# card-terminal.net
KiCad netlist of a schematic drawn in EAGLE
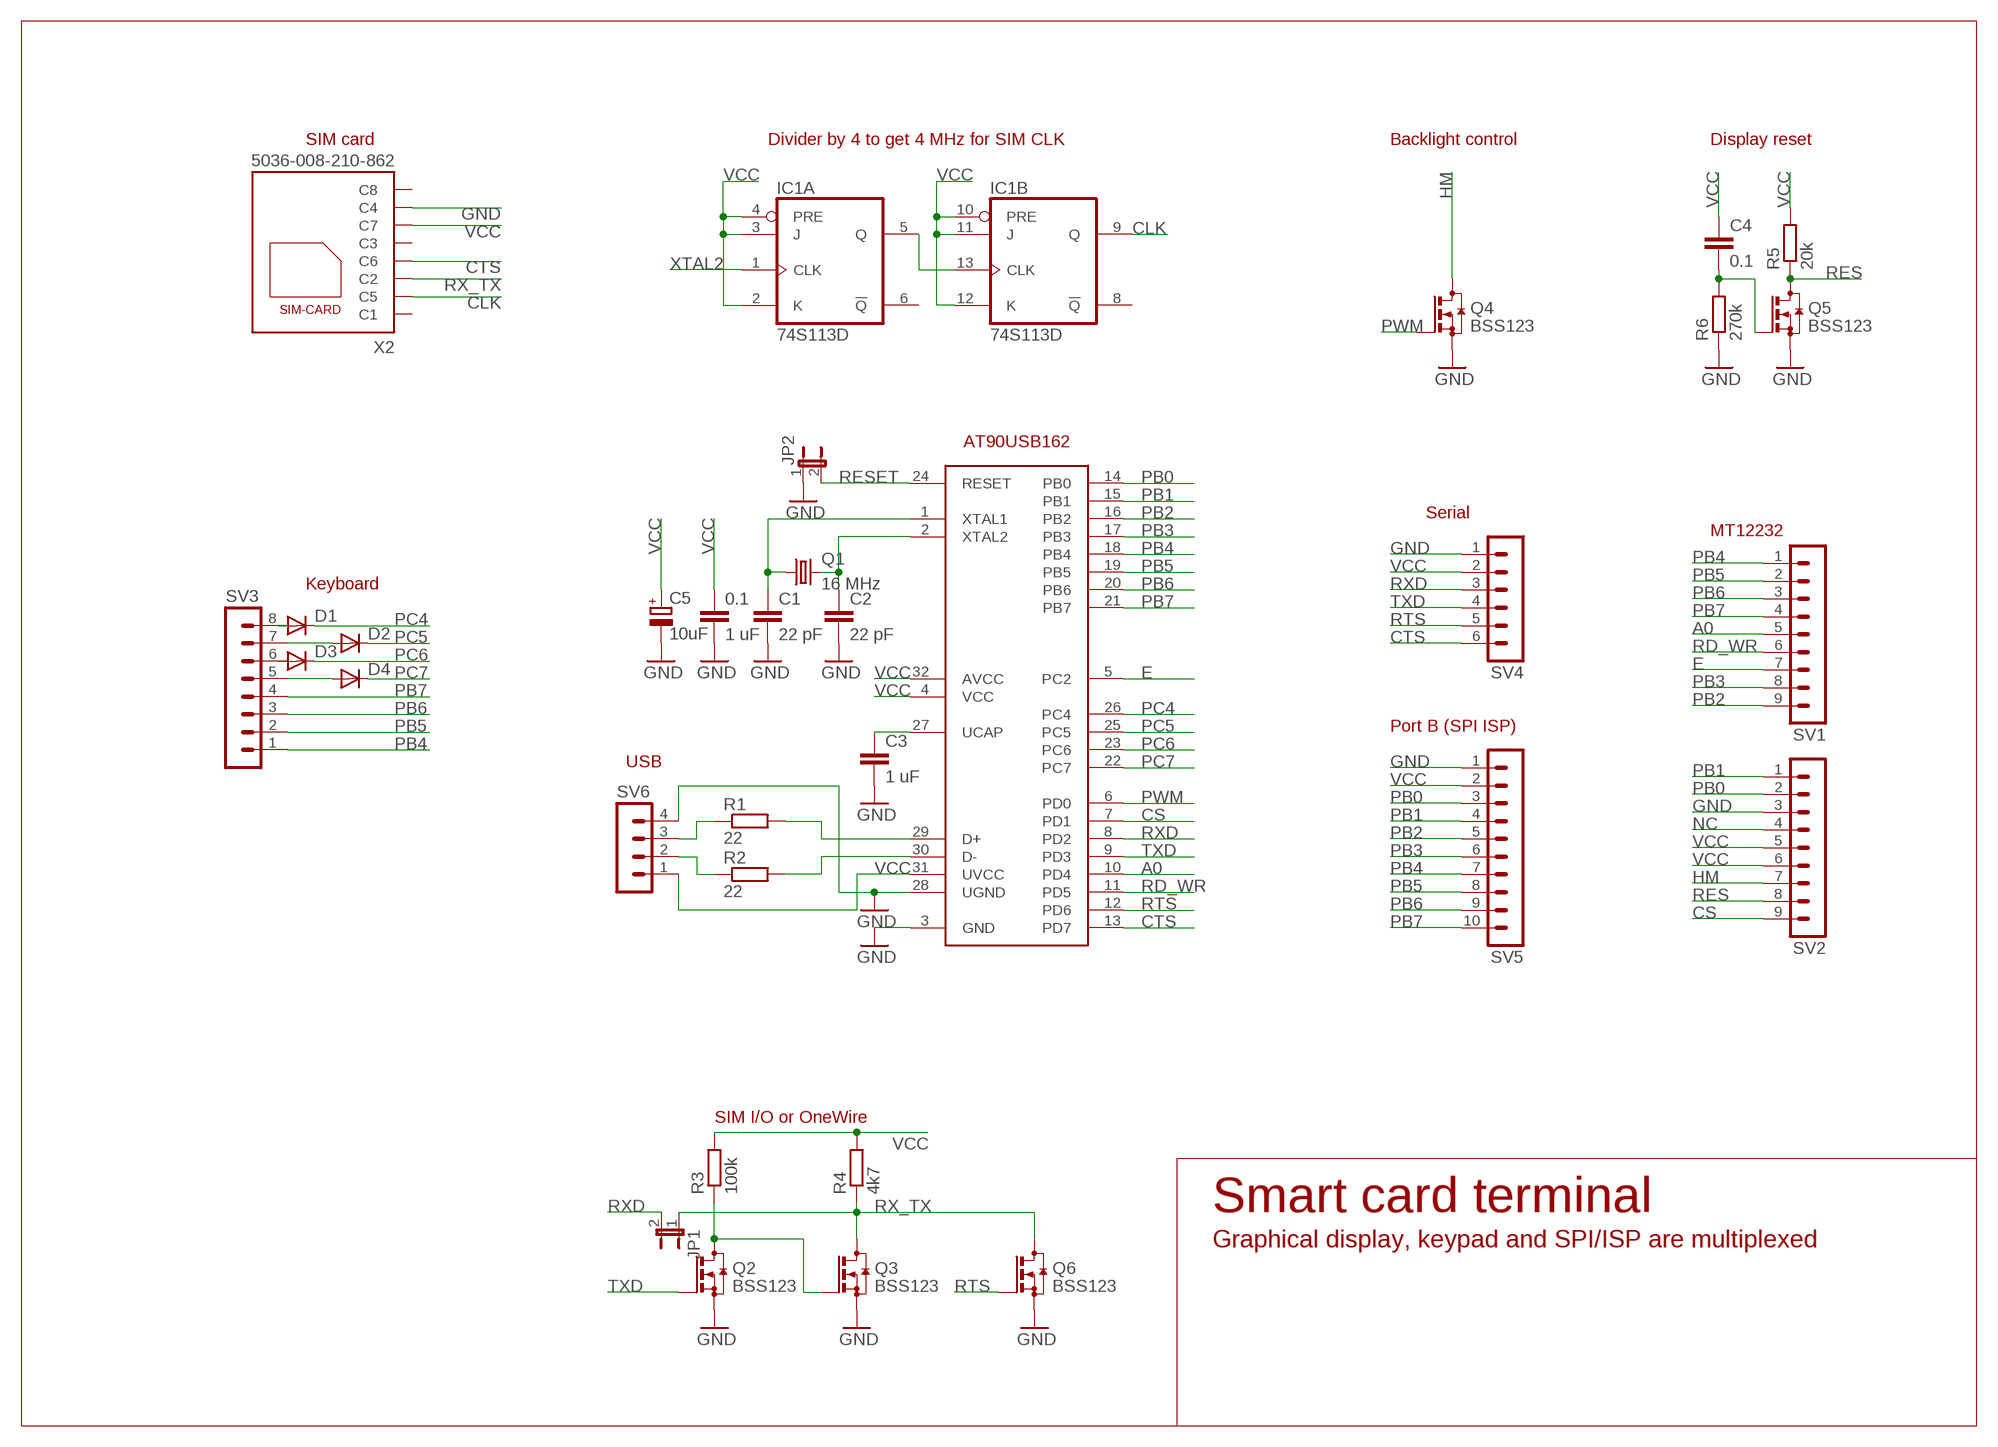
[diagram p0: schematic, sheet 1]

(export (version "E")
  (design (tool "Eeschema 10.0.6"))
  (components
    (comp (ref "0.1")
      (value "1 uF")
      (footprint "eagle-import:C0805")
      (libsource (lib "eagle-import") (part "C-EUC0805"))
    )
    (comp (ref "C1")
      (value "22 pF")
      (footprint "eagle-import:C0805")
      (libsource (lib "eagle-import") (part "C-EUC0805"))
    )
    (comp (ref "C2")
      (value "22 pF")
      (footprint "eagle-import:C0805")
      (libsource (lib "eagle-import") (part "C-EUC0805"))
    )
    (comp (ref "C3")
      (value "1 uF")
      (footprint "eagle-import:C0805")
      (libsource (lib "eagle-import") (part "C-EUC0805"))
    )
    (comp (ref "C4")
      (value "0.1")
      (footprint "eagle-import:C0805")
      (libsource (lib "eagle-import") (part "C-EUC0805"))
    )
    (comp (ref "C5")
      (value "10uF")
      (footprint "eagle-import:153CLV-0505")
      (libsource (lib "eagle-import") (part "CPOL-EU153CLV-0505"))
    )
    (comp (ref "D1")
      (value "DIODE-MINIMELF")
      (footprint "eagle-import:MINIMELF")
      (libsource (lib "eagle-import") (part "DIODE-MINIMELF"))
    )
    (comp (ref "D2")
      (value "DIODE-MINIMELF")
      (footprint "eagle-import:MINIMELF")
      (libsource (lib "eagle-import") (part "DIODE-MINIMELF"))
    )
    (comp (ref "D3")
      (value "DIODE-MINIMELF")
      (footprint "eagle-import:MINIMELF")
      (libsource (lib "eagle-import") (part "DIODE-MINIMELF"))
    )
    (comp (ref "D4")
      (value "DIODE-MINIMELF")
      (footprint "eagle-import:MINIMELF")
      (libsource (lib "eagle-import") (part "DIODE-MINIMELF"))
    )
    (comp (ref "IC1")
      (value "74S113D")
      (footprint "eagle-import:SO14")
      (libsource (lib "eagle-import") (part "74113DS"))
    )
    (comp (ref "JP1")
      (value "JP1E")
      (footprint "eagle-import:JP1")
      (libsource (lib "eagle-import") (part "JP1E"))
    )
    (comp (ref "JP2")
      (value "JP1E")
      (footprint "eagle-import:JP1")
      (libsource (lib "eagle-import") (part "JP1E"))
    )
    (comp (ref "Q1")
      (value "16 MHz")
      (footprint "eagle-import:HC49_S")
      (libsource (lib "eagle-import") (part "CRYSTALHC49S"))
    )
    (comp (ref "Q2")
      (value "BSS123")
      (footprint "eagle-import:SOT23")
      (libsource (lib "eagle-import") (part "BSS123"))
    )
    (comp (ref "Q3")
      (value "BSS123")
      (footprint "eagle-import:SOT23")
      (libsource (lib "eagle-import") (part "BSS123"))
    )
    (comp (ref "Q4")
      (value "BSS123")
      (footprint "eagle-import:SOT23")
      (libsource (lib "eagle-import") (part "BSS123"))
    )
    (comp (ref "Q5")
      (value "BSS123")
      (footprint "eagle-import:SOT23")
      (libsource (lib "eagle-import") (part "BSS123"))
    )
    (comp (ref "Q6")
      (value "BSS123")
      (footprint "eagle-import:SOT23")
      (libsource (lib "eagle-import") (part "BSS123"))
    )
    (comp (ref "R1")
      (value "22")
      (footprint "eagle-import:M0805")
      (libsource (lib "eagle-import") (part "R-EU_M0805"))
    )
    (comp (ref "R2")
      (value "22")
      (footprint "eagle-import:M0805")
      (libsource (lib "eagle-import") (part "R-EU_M0805"))
    )
    (comp (ref "R3")
      (value "100k")
      (footprint "eagle-import:M0805")
      (libsource (lib "eagle-import") (part "R-EU_M0805"))
    )
    (comp (ref "R4")
      (value "4k7")
      (footprint "eagle-import:M0805")
      (libsource (lib "eagle-import") (part "R-EU_M0805"))
    )
    (comp (ref "R5")
      (value "20k")
      (footprint "eagle-import:M0805")
      (libsource (lib "eagle-import") (part "R-EU_M0805"))
    )
    (comp (ref "R6")
      (value "270k")
      (footprint "eagle-import:M0805")
      (libsource (lib "eagle-import") (part "R-EU_M0805"))
    )
    (comp (ref "SV1")
      (value "MA09-1W")
      (footprint "eagle-import:MA09-1W")
      (libsource (lib "eagle-import") (part "MA09-1W"))
    )
    (comp (ref "SV2")
      (value "MA09-1W")
      (footprint "eagle-import:MA09-1W")
      (libsource (lib "eagle-import") (part "MA09-1W"))
    )
    (comp (ref "SV3")
      (value "MA08-1")
      (footprint "eagle-import:MA08-1")
      (libsource (lib "eagle-import") (part "MA08-1"))
    )
    (comp (ref "SV4")
      (value "MA06-1")
      (footprint "eagle-import:MA06-1")
      (libsource (lib "eagle-import") (part "MA06-1"))
    )
    (comp (ref "SV5")
      (value "MA10-1W")
      (footprint "eagle-import:MA10-1W")
      (libsource (lib "eagle-import") (part "MA10-1W"))
    )
    (comp (ref "SV6")
      (value "MA04-1")
      (footprint "eagle-import:MA04-1")
      (libsource (lib "eagle-import") (part "MA04-1"))
    )
    (comp (ref "U$1")
      (value "AT90USB162")
      (footprint "eagle-import:VQFP32")
      (libsource (lib "eagle-import") (part "AT90USB162"))
    )
    (comp (ref "X2")
      (value "5036-008-210-862")
      (footprint "eagle-import:5036_008_210_862")
      (libsource (lib "eagle-import") (part "5036-008-210-862"))
    )
  )
  (nets
    (net (code "1") (name "/A0") (class "Default")
      (node (ref "SV1") (pin "5") (pinfunction "5_5") (pintype "passive"))
      (node (ref "U$1") (pin "10") (pinfunction "PD4_10") (pintype "bidirectional"))
    )
    (net (code "2") (name "/CLK") (class "Default")
      (node (ref "IC1") (pin "9") (pinfunction "Q_9") (pintype "output"))
      (node (ref "X2") (pin "C5") (pinfunction "C5_C5") (pintype "passive"))
    )
    (net (code "3") (name "/CS") (class "Default")
      (node (ref "SV2") (pin "9") (pinfunction "9_9") (pintype "passive"))
      (node (ref "U$1") (pin "7") (pinfunction "PD1_7") (pintype "bidirectional"))
    )
    (net (code "4") (name "/CTS") (class "Default")
      (node (ref "SV4") (pin "6") (pinfunction "6_6") (pintype "passive"))
      (node (ref "U$1") (pin "13") (pinfunction "PD7_13") (pintype "bidirectional"))
      (node (ref "X2") (pin "C6") (pinfunction "C6_C6") (pintype "passive"))
    )
    (net (code "5") (name "/E") (class "Default")
      (node (ref "SV1") (pin "7") (pinfunction "7_7") (pintype "passive"))
      (node (ref "U$1") (pin "5") (pinfunction "PC2_5") (pintype "bidirectional"))
    )
    (net (code "6") (name "/HM") (class "Default")
      (node (ref "Q4") (pin "3") (pinfunction "D_3") (pintype "passive"))
      (node (ref "SV2") (pin "7") (pinfunction "7_7") (pintype "passive"))
    )
    (net (code "7") (name "/NC") (class "Default")
      (node (ref "SV2") (pin "4") (pinfunction "4_4") (pintype "passive"))
    )
    (net (code "8") (name "/PB0") (class "Default")
      (node (ref "SV2") (pin "2") (pinfunction "2_2") (pintype "passive"))
      (node (ref "SV5") (pin "3") (pinfunction "3_3") (pintype "passive"))
      (node (ref "U$1") (pin "14") (pinfunction "PB0_14") (pintype "bidirectional"))
    )
    (net (code "9") (name "/PB1") (class "Default")
      (node (ref "SV2") (pin "1") (pinfunction "1_1") (pintype "passive"))
      (node (ref "SV5") (pin "4") (pinfunction "4_4") (pintype "passive"))
      (node (ref "U$1") (pin "15") (pinfunction "PB1_15") (pintype "bidirectional"))
    )
    (net (code "10") (name "/PB2") (class "Default")
      (node (ref "SV1") (pin "9") (pinfunction "9_9") (pintype "passive"))
      (node (ref "SV5") (pin "5") (pinfunction "5_5") (pintype "passive"))
      (node (ref "U$1") (pin "16") (pinfunction "PB2_16") (pintype "bidirectional"))
    )
    (net (code "11") (name "/PB3") (class "Default")
      (node (ref "SV1") (pin "8") (pinfunction "8_8") (pintype "passive"))
      (node (ref "SV5") (pin "6") (pinfunction "6_6") (pintype "passive"))
      (node (ref "U$1") (pin "17") (pinfunction "PB3_17") (pintype "bidirectional"))
    )
    (net (code "12") (name "/PB4") (class "Default")
      (node (ref "SV1") (pin "1") (pinfunction "1_1") (pintype "passive"))
      (node (ref "SV3") (pin "1") (pinfunction "1_1") (pintype "passive"))
      (node (ref "SV5") (pin "7") (pinfunction "7_7") (pintype "passive"))
      (node (ref "U$1") (pin "18") (pinfunction "PB4_18") (pintype "bidirectional"))
    )
    (net (code "13") (name "/PB5") (class "Default")
      (node (ref "SV1") (pin "2") (pinfunction "2_2") (pintype "passive"))
      (node (ref "SV3") (pin "2") (pinfunction "2_2") (pintype "passive"))
      (node (ref "SV5") (pin "8") (pinfunction "8_8") (pintype "passive"))
      (node (ref "U$1") (pin "19") (pinfunction "PB5_19") (pintype "bidirectional"))
    )
    (net (code "14") (name "/PB6") (class "Default")
      (node (ref "SV1") (pin "3") (pinfunction "3_3") (pintype "passive"))
      (node (ref "SV3") (pin "3") (pinfunction "3_3") (pintype "passive"))
      (node (ref "SV5") (pin "9") (pinfunction "9_9") (pintype "passive"))
      (node (ref "U$1") (pin "20") (pinfunction "PB6_20") (pintype "bidirectional"))
    )
    (net (code "15") (name "/PB7") (class "Default")
      (node (ref "SV1") (pin "4") (pinfunction "4_4") (pintype "passive"))
      (node (ref "SV3") (pin "4") (pinfunction "4_4") (pintype "passive"))
      (node (ref "SV5") (pin "10") (pinfunction "10_10") (pintype "passive"))
      (node (ref "U$1") (pin "21") (pinfunction "PB7_21") (pintype "bidirectional"))
    )
    (net (code "16") (name "/PC4") (class "Default")
      (node (ref "D1") (pin "C") (pinfunction "C_C") (pintype "passive"))
      (node (ref "U$1") (pin "26") (pinfunction "PC4_26") (pintype "bidirectional"))
    )
    (net (code "17") (name "/PC5") (class "Default")
      (node (ref "D2") (pin "C") (pinfunction "C_C") (pintype "passive"))
      (node (ref "U$1") (pin "25") (pinfunction "PC5_25") (pintype "bidirectional"))
    )
    (net (code "18") (name "/PC6") (class "Default")
      (node (ref "D3") (pin "C") (pinfunction "C_C") (pintype "passive"))
      (node (ref "U$1") (pin "23") (pinfunction "PC6_23") (pintype "bidirectional"))
    )
    (net (code "19") (name "/PC7") (class "Default")
      (node (ref "D4") (pin "C") (pinfunction "C_C") (pintype "passive"))
      (node (ref "U$1") (pin "22") (pinfunction "PC7_22") (pintype "bidirectional"))
    )
    (net (code "20") (name "/PWM") (class "Default")
      (node (ref "Q4") (pin "1") (pinfunction "G_1") (pintype "passive"))
      (node (ref "U$1") (pin "6") (pinfunction "PD0_6") (pintype "bidirectional"))
    )
    (net (code "21") (name "/RD_WR") (class "Default")
      (node (ref "SV1") (pin "6") (pinfunction "6_6") (pintype "passive"))
      (node (ref "U$1") (pin "11") (pinfunction "PD5_11") (pintype "bidirectional"))
    )
    (net (code "22") (name "/RES") (class "Default")
      (node (ref "Q5") (pin "3") (pinfunction "D_3") (pintype "passive"))
      (node (ref "R5") (pin "1") (pinfunction "1_1") (pintype "passive"))
      (node (ref "SV2") (pin "8") (pinfunction "8_8") (pintype "passive"))
    )
    (net (code "23") (name "/RESET") (class "Default")
      (node (ref "JP2") (pin "2") (pinfunction "2_2") (pintype "passive"))
      (node (ref "U$1") (pin "24") (pinfunction "RESET_24") (pintype "bidirectional"))
    )
    (net (code "24") (name "/RTS") (class "Default")
      (node (ref "Q6") (pin "1") (pinfunction "G_1") (pintype "passive"))
      (node (ref "SV4") (pin "5") (pinfunction "5_5") (pintype "passive"))
      (node (ref "U$1") (pin "12") (pinfunction "PD6_12") (pintype "bidirectional"))
    )
    (net (code "25") (name "/RXD") (class "Default")
      (node (ref "JP1") (pin "2") (pinfunction "2_2") (pintype "passive"))
      (node (ref "SV4") (pin "3") (pinfunction "3_3") (pintype "passive"))
      (node (ref "U$1") (pin "8") (pinfunction "PD2_8") (pintype "bidirectional"))
    )
    (net (code "26") (name "/RX_TX") (class "Default")
      (node (ref "JP1") (pin "1") (pinfunction "1_1") (pintype "passive"))
      (node (ref "Q3") (pin "3") (pinfunction "D_3") (pintype "passive"))
      (node (ref "Q6") (pin "3") (pinfunction "D_3") (pintype "passive"))
      (node (ref "R4") (pin "1") (pinfunction "1_1") (pintype "passive"))
      (node (ref "X2") (pin "C2") (pinfunction "C2_C2") (pintype "passive"))
    )
    (net (code "27") (name "/TXD") (class "Default")
      (node (ref "Q2") (pin "1") (pinfunction "G_1") (pintype "passive"))
      (node (ref "SV4") (pin "4") (pinfunction "4_4") (pintype "passive"))
      (node (ref "U$1") (pin "9") (pinfunction "PD3_9") (pintype "bidirectional"))
    )
    (net (code "28") (name "/VCC") (class "Default")
      (node (ref "0.1") (pin "1") (pinfunction "1_1") (pintype "passive"))
      (node (ref "C4") (pin "1") (pinfunction "1_1") (pintype "passive"))
      (node (ref "C5") (pin "+") (pinfunction "+_+") (pintype "passive"))
      (node (ref "IC1") (pin "10") (pinfunction "PRE_10") (pintype "input"))
      (node (ref "IC1") (pin "11") (pinfunction "J_11") (pintype "input"))
      (node (ref "IC1") (pin "12") (pinfunction "K_12") (pintype "input"))
      (node (ref "IC1") (pin "2") (pinfunction "K_2") (pintype "input"))
      (node (ref "IC1") (pin "3") (pinfunction "J_3") (pintype "input"))
      (node (ref "IC1") (pin "4") (pinfunction "PRE_4") (pintype "input"))
      (node (ref "R3") (pin "2") (pinfunction "2_2") (pintype "passive"))
      (node (ref "R4") (pin "2") (pinfunction "2_2") (pintype "passive"))
      (node (ref "R5") (pin "2") (pinfunction "2_2") (pintype "passive"))
      (node (ref "SV2") (pin "5") (pinfunction "5_5") (pintype "passive"))
      (node (ref "SV2") (pin "6") (pinfunction "6_6") (pintype "passive"))
      (node (ref "SV4") (pin "2") (pinfunction "2_2") (pintype "passive"))
      (node (ref "SV5") (pin "2") (pinfunction "2_2") (pintype "passive"))
      (node (ref "SV6") (pin "1") (pinfunction "1_1") (pintype "passive"))
      (node (ref "U$1") (pin "31") (pinfunction "UVCC_31") (pintype "bidirectional"))
      (node (ref "U$1") (pin "32") (pinfunction "AVCC_32") (pintype "bidirectional"))
      (node (ref "U$1") (pin "4") (pinfunction "VCC_4") (pintype "power_in"))
      (node (ref "X2") (pin "C7") (pinfunction "C7_C7") (pintype "passive"))
    )
    (net (code "29") (name "/XTAL2") (class "Default")
      (node (ref "C2") (pin "1") (pinfunction "1_1") (pintype "passive"))
      (node (ref "IC1") (pin "1") (pinfunction "CLK_1") (pintype "input"))
      (node (ref "Q1") (pin "2") (pinfunction "2_2") (pintype "passive"))
      (node (ref "U$1") (pin "2") (pinfunction "XTAL2_2") (pintype "bidirectional"))
    )
    (net (code "30") (name "GND") (class "Default")
      (node (ref "0.1") (pin "2") (pinfunction "2_2") (pintype "passive"))
      (node (ref "C1") (pin "2") (pinfunction "2_2") (pintype "passive"))
      (node (ref "C2") (pin "2") (pinfunction "2_2") (pintype "passive"))
      (node (ref "C3") (pin "2") (pinfunction "2_2") (pintype "passive"))
      (node (ref "C5") (pin "-") (pinfunction "-_-") (pintype "passive"))
      (node (ref "JP2") (pin "1") (pinfunction "1_1") (pintype "passive"))
      (node (ref "Q2") (pin "2") (pinfunction "S_2") (pintype "passive"))
      (node (ref "Q3") (pin "2") (pinfunction "S_2") (pintype "passive"))
      (node (ref "Q4") (pin "2") (pinfunction "S_2") (pintype "passive"))
      (node (ref "Q5") (pin "2") (pinfunction "S_2") (pintype "passive"))
      (node (ref "Q6") (pin "2") (pinfunction "S_2") (pintype "passive"))
      (node (ref "R6") (pin "1") (pinfunction "1_1") (pintype "passive"))
      (node (ref "SV2") (pin "3") (pinfunction "3_3") (pintype "passive"))
      (node (ref "SV4") (pin "1") (pinfunction "1_1") (pintype "passive"))
      (node (ref "SV5") (pin "1") (pinfunction "1_1") (pintype "passive"))
      (node (ref "SV6") (pin "4") (pinfunction "4_4") (pintype "passive"))
      (node (ref "U$1") (pin "28") (pinfunction "UGND_28") (pintype "bidirectional"))
      (node (ref "U$1") (pin "3") (pinfunction "GND_3") (pintype "power_in"))
      (node (ref "X2") (pin "C4") (pinfunction "C4_C4") (pintype "passive"))
    )
    (net (code "31") (name "Net-(D1-PadA)") (class "Default")
      (node (ref "D1") (pin "A") (pinfunction "A_A") (pintype "passive"))
      (node (ref "SV3") (pin "8") (pinfunction "8_8") (pintype "passive"))
    )
    (net (code "32") (name "Net-(D2-PadA)") (class "Default")
      (node (ref "D2") (pin "A") (pinfunction "A_A") (pintype "passive"))
      (node (ref "SV3") (pin "7") (pinfunction "7_7") (pintype "passive"))
    )
    (net (code "33") (name "Net-(D3-PadA)") (class "Default")
      (node (ref "D3") (pin "A") (pinfunction "A_A") (pintype "passive"))
      (node (ref "SV3") (pin "6") (pinfunction "6_6") (pintype "passive"))
    )
    (net (code "34") (name "Net-(D4-PadA)") (class "Default")
      (node (ref "D4") (pin "A") (pinfunction "A_A") (pintype "passive"))
      (node (ref "SV3") (pin "5") (pinfunction "5_5") (pintype "passive"))
    )
    (net (code "35") (name "Net-(IC1A-Q)") (class "Default")
      (node (ref "IC1") (pin "13") (pinfunction "CLK_13") (pintype "input"))
      (node (ref "IC1") (pin "5") (pinfunction "Q_5") (pintype "output"))
    )
    (net (code "36") (name "Net-(Q2-D)") (class "Default")
      (node (ref "Q2") (pin "3") (pinfunction "D_3") (pintype "passive"))
      (node (ref "Q3") (pin "1") (pinfunction "G_1") (pintype "passive"))
      (node (ref "R3") (pin "1") (pinfunction "1_1") (pintype "passive"))
    )
    (net (code "37") (name "Net-(Q5-G)") (class "Default")
      (node (ref "C4") (pin "2") (pinfunction "2_2") (pintype "passive"))
      (node (ref "Q5") (pin "1") (pinfunction "G_1") (pintype "passive"))
      (node (ref "R6") (pin "2") (pinfunction "2_2") (pintype "passive"))
    )
    (net (code "38") (name "Net-(R1-Pad1)") (class "Default")
      (node (ref "R1") (pin "1") (pinfunction "1_1") (pintype "passive"))
      (node (ref "SV6") (pin "3") (pinfunction "3_3") (pintype "passive"))
    )
    (net (code "39") (name "Net-(R2-Pad1)") (class "Default")
      (node (ref "R2") (pin "1") (pinfunction "1_1") (pintype "passive"))
      (node (ref "SV6") (pin "2") (pinfunction "2_2") (pintype "passive"))
    )
    (net (code "40") (name "Net-(U$1-D+)") (class "Default")
      (node (ref "R1") (pin "2") (pinfunction "2_2") (pintype "passive"))
      (node (ref "U$1") (pin "29") (pinfunction "D+_29") (pintype "bidirectional"))
    )
    (net (code "41") (name "Net-(U$1-D-)") (class "Default")
      (node (ref "R2") (pin "2") (pinfunction "2_2") (pintype "passive"))
      (node (ref "U$1") (pin "30") (pinfunction "D-_30") (pintype "bidirectional"))
    )
    (net (code "42") (name "Net-(U$1-UCAP)") (class "Default")
      (node (ref "C3") (pin "1") (pinfunction "1_1") (pintype "passive"))
      (node (ref "U$1") (pin "27") (pinfunction "UCAP_27") (pintype "bidirectional"))
    )
    (net (code "43") (name "Net-(U$1-XTAL1)") (class "Default")
      (node (ref "C1") (pin "1") (pinfunction "1_1") (pintype "passive"))
      (node (ref "Q1") (pin "1") (pinfunction "1_1") (pintype "passive"))
      (node (ref "U$1") (pin "1") (pinfunction "XTAL1_1") (pintype "bidirectional"))
    )
    (net (code "44") (name "unconnected-(IC1A-~{Q}-Pad6)") (class "Default")
      (node (ref "IC1") (pin "6") (pinfunction "~{Q}_6") (pintype "output"))
    )
    (net (code "45") (name "unconnected-(IC1B-~{Q}-Pad8)") (class "Default")
      (node (ref "IC1") (pin "8") (pinfunction "~{Q}_8") (pintype "output"))
    )
    (net (code "46") (name "unconnected-(X2-PadC1)") (class "Default")
      (node (ref "X2") (pin "C1") (pinfunction "C1_C1") (pintype "passive"))
    )
    (net (code "47") (name "unconnected-(X2-PadC3)") (class "Default")
      (node (ref "X2") (pin "C3") (pinfunction "C3_C3") (pintype "passive"))
    )
    (net (code "48") (name "unconnected-(X2-PadC8)") (class "Default")
      (node (ref "X2") (pin "C8") (pinfunction "C8_C8") (pintype "passive"))
    )
  )
)
